# pressure_gage.net
KiCad netlist of a schematic drawn in Altium Designer
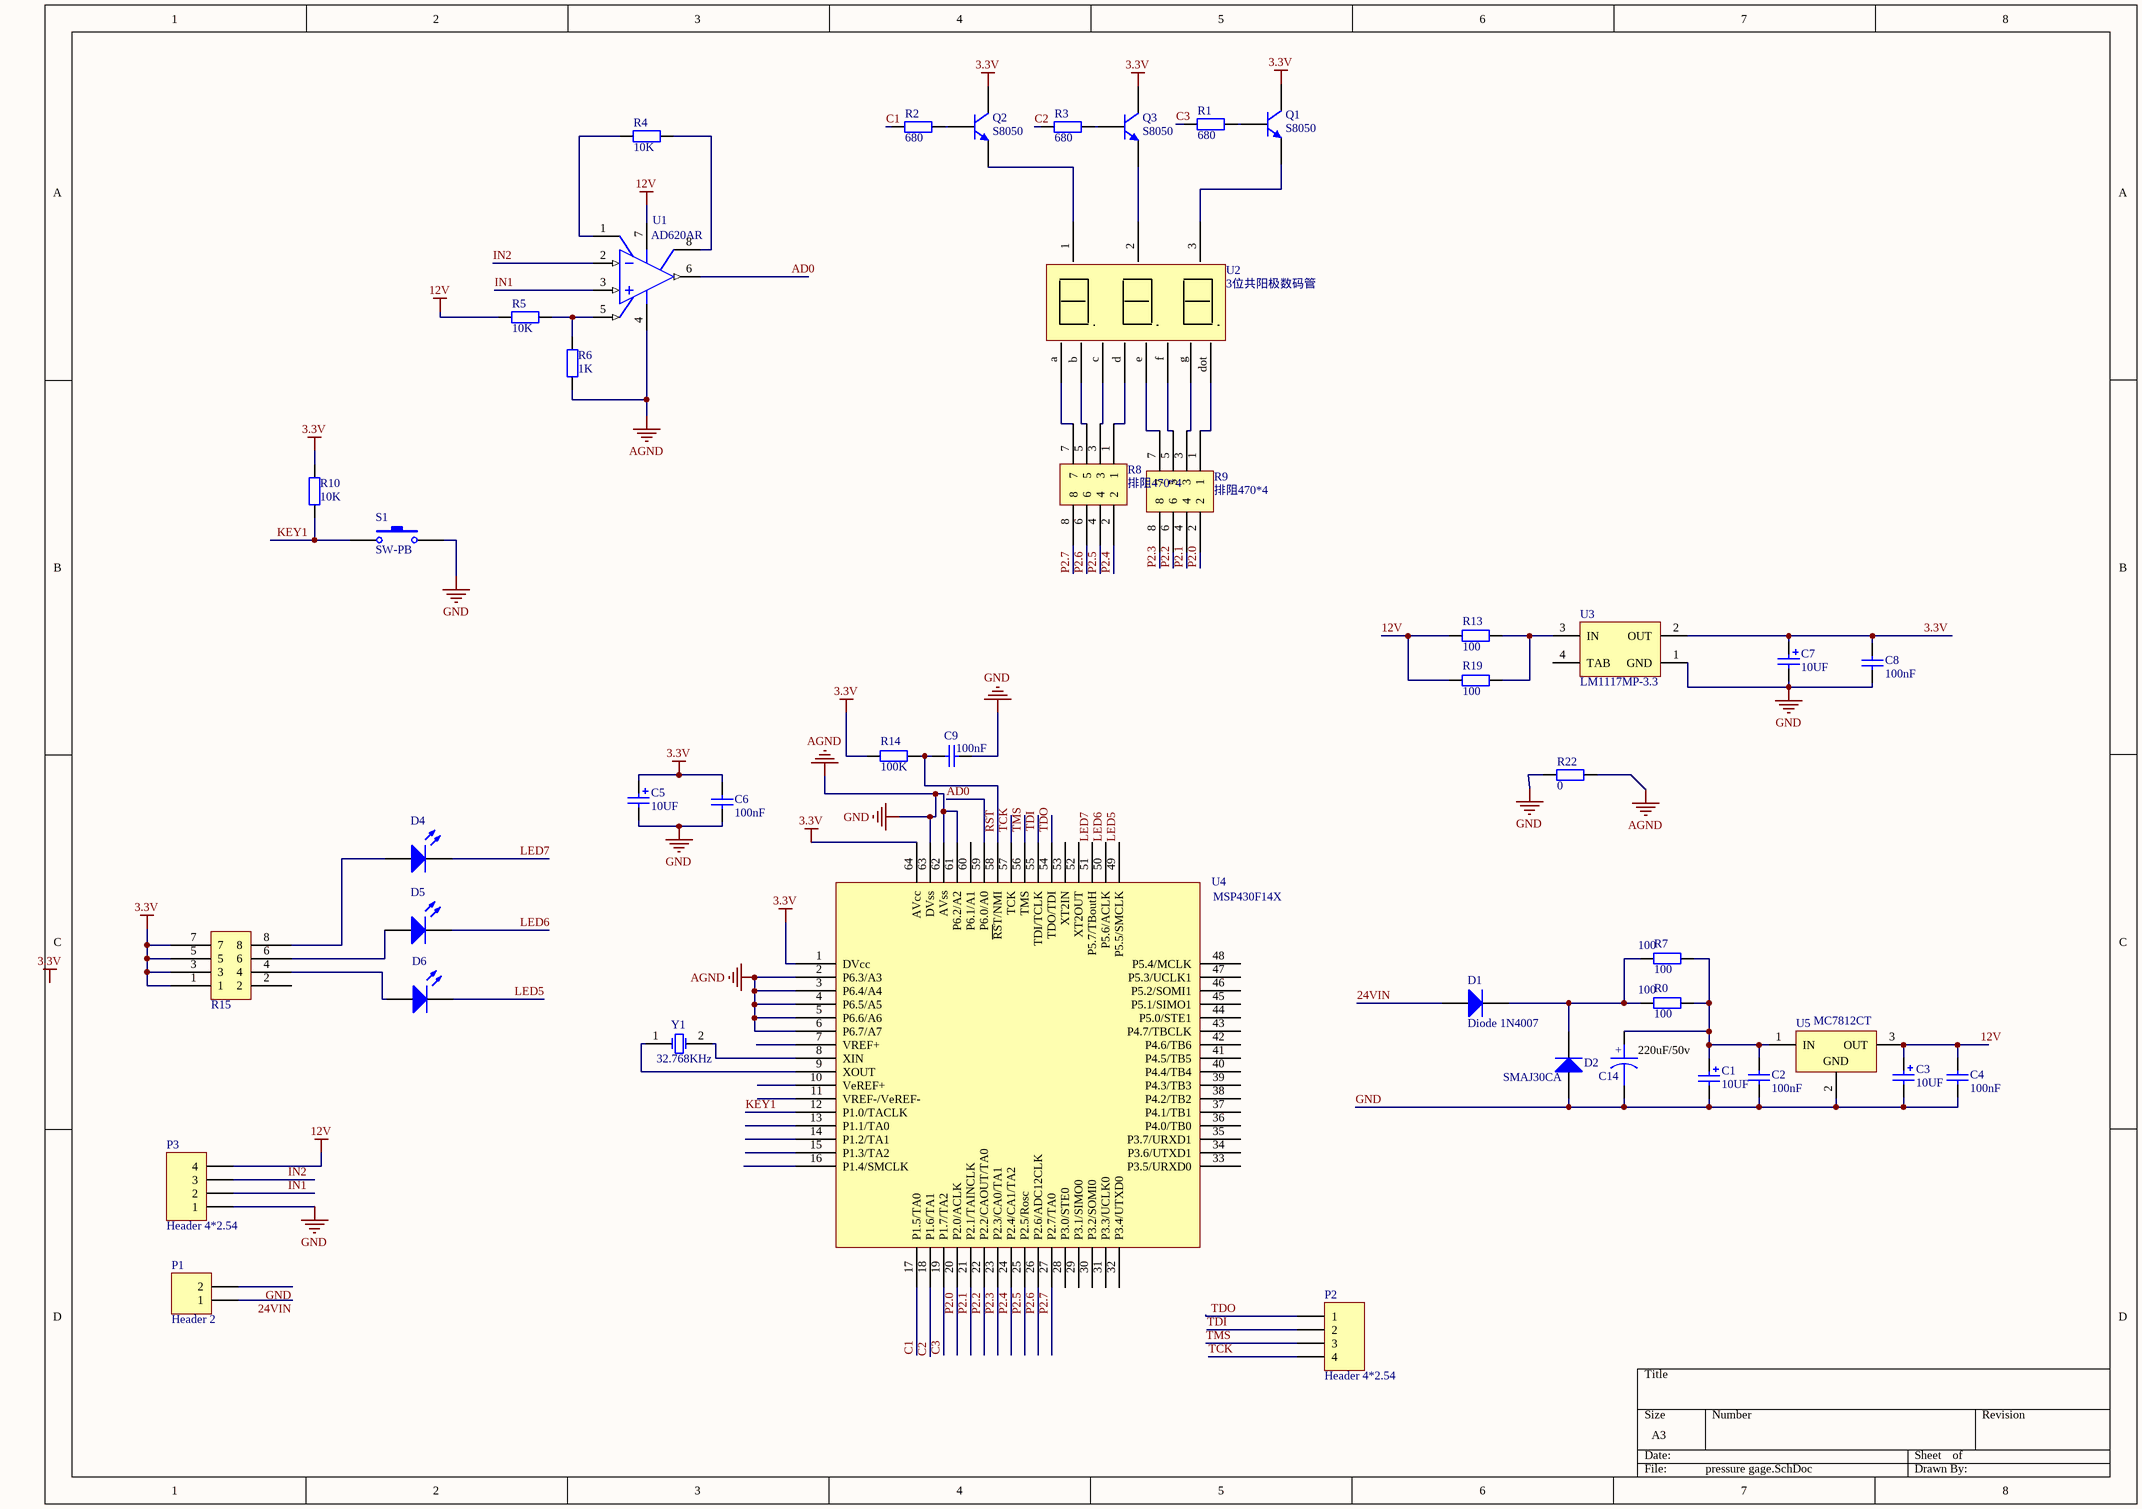
[diagram p0: pressure gage.SchDoc]

(export (version "E")
  (design (tool "Eeschema 10.0.6"))
  (components
    (comp (ref "C1")
      (value "10UF")
      (footprint "3216")
      (description "Polarized Capacitor (Axial)")
      (fields (field (name "Comment") "10uf") (field (name "PUBLISHER") "Altium Limited"))
      (libsource (lib "Miscellaneous Devices") (part "Cap Pol2"))
    )
    (comp (ref "C2")
      (value "100nF")
      (footprint "0805_C_Y")
      (description "Capacitor")
      (fields (field (name "Comment") "100nf") (field (name "PUBLISHER") "Altium Limited"))
      (libsource (lib "Miscellaneous Devices") (part "Cap"))
    )
    (comp (ref "C3")
      (value "10UF")
      (footprint "3216")
      (description "Polarized Capacitor (Axial)")
      (fields (field (name "Comment") "10uf") (field (name "PUBLISHER") "Altium Limited"))
      (libsource (lib "Miscellaneous Devices") (part "Cap Pol2"))
    )
    (comp (ref "C4")
      (value "100nF")
      (footprint "0805_C_Y")
      (description "Capacitor")
      (fields (field (name "Comment") "100nf") (field (name "PUBLISHER") "Altium Limited"))
      (libsource (lib "Miscellaneous Devices") (part "Cap"))
    )
    (comp (ref "C5")
      (value "10UF")
      (footprint "3216")
      (description "Polarized Capacitor (Axial)")
      (fields (field (name "Comment") "10uf") (field (name "PUBLISHER") "Altium Limited"))
      (libsource (lib "Miscellaneous Devices") (part "Cap Pol2"))
    )
    (comp (ref "C6")
      (value "100nF")
      (footprint "0603AC")
      (description "Capacitor")
      (fields (field (name "Comment") "100nf") (field (name "PUBLISHER") "Altium Limited"))
      (libsource (lib "Miscellaneous Devices") (part "Cap"))
    )
    (comp (ref "C7")
      (value "10UF")
      (footprint "3216")
      (description "Polarized Capacitor (Axial)")
      (fields (field (name "Comment") "10uf") (field (name "PUBLISHER") "Altium Limited"))
      (libsource (lib "Miscellaneous Devices") (part "Cap Pol2"))
    )
    (comp (ref "C8")
      (value "100nF")
      (footprint "0603AC")
      (description "Capacitor")
      (fields (field (name "Comment") "100nf") (field (name "PUBLISHER") "Altium Limited"))
      (libsource (lib "Miscellaneous Devices") (part "Cap"))
    )
    (comp (ref "C9")
      (value "100nF")
      (footprint "0603AC")
      (description "Capacitor")
      (fields (field (name "Comment") "100nf") (field (name "PUBLISHER") "Altium Limited"))
      (libsource (lib "Miscellaneous Devices") (part "Cap"))
    )
    (comp (ref "C14")
      (value "220uF/50v")
      (footprint "D50")
      (description "Capacitor")
      (libsource (lib "*") (part "CAPACITOR POL"))
    )
    (comp (ref "D1")
      (value "Diode 1N4007")
      (footprint "DO-214")
      (description "1 Amp General Purpose Rectifier")
      (fields (field (name "PUBLISHER") "Altium Limited"))
      (libsource (lib "Miscellaneous Devices") (part "Diode 1N4007"))
    )
    (comp (ref "D2")
      (value "SMAJ30CA")
      (footprint "1812")
      (description "3 Amp General Purpose Rectifier")
      (fields (field (name "PUBLISHER") "Altium Limited"))
      (libsource (lib "Miscellaneous Devices") (part "Diode 1N5402"))
    )
    (comp (ref "D4")
      (value "LED")
      (footprint "LED")
      (description "Typical INFRARED GaAs LED")
      (fields (field (name "PUBLISHER") "Altium Limited"))
      (libsource (lib "Miscellaneous Devices") (part "LED0"))
    )
    (comp (ref "D5")
      (value "LED")
      (footprint "LED")
      (description "Typical INFRARED GaAs LED")
      (fields (field (name "PUBLISHER") "Altium Limited"))
      (libsource (lib "Miscellaneous Devices") (part "LED0"))
    )
    (comp (ref "D6")
      (value "LED")
      (footprint "LED")
      (description "Typical INFRARED GaAs LED")
      (fields (field (name "PUBLISHER") "Altium Limited"))
      (libsource (lib "Miscellaneous Devices") (part "LED0"))
    )
    (comp (ref "P1")
      (value "Header 2")
      (footprint "HDR1X2")
      (description "Header, 2-Pin")
      (fields (field (name "PUBLISHER") "Altium Limited"))
      (libsource (lib "Miscellaneous Connectors") (part "Header 2"))
    )
    (comp (ref "P2")
      (value "Header 4*2.54")
      (footprint "HDR1X4")
      (description "Header, 4-Pin")
      (fields (field (name "PUBLISHER") "Altium Limited"))
      (libsource (lib "") (part "Header 4_1"))
    )
    (comp (ref "P3")
      (value "Header 4*2.54")
      (footprint "HDR1X4")
      (description "Header, 4-Pin")
      (fields (field (name "PUBLISHER") "Altium Limited"))
      (libsource (lib "Miscellaneous Connectors") (part "Header 4"))
    )
    (comp (ref "Q1")
      (value "S8050")
      (footprint "SOT-23_Y")
      (description "NPN General Purpose Amplifier")
      (fields (field (name "PUBLISHER") "Altium Limited"))
      (libsource (lib "Miscellaneous Devices") (part "2N3904"))
    )
    (comp (ref "Q2")
      (value "S8050")
      (footprint "SOT-23_Y")
      (description "NPN General Purpose Amplifier")
      (fields (field (name "PUBLISHER") "Altium Limited"))
      (libsource (lib "Miscellaneous Devices") (part "2N3904"))
    )
    (comp (ref "Q3")
      (value "S8050")
      (footprint "SOT-23_Y")
      (description "NPN General Purpose Amplifier")
      (fields (field (name "PUBLISHER") "Altium Limited"))
      (libsource (lib "Miscellaneous Devices") (part "2N3904"))
    )
    (comp (ref "R0")
      (value "100")
      (footprint "1206")
      (description "Resistor")
      (fields (field (name "ALTIUM_VALUE") "100") (field (name "PUBLISHER") "Altium Limited"))
      (libsource (lib "") (part "Res2_1"))
    )
    (comp (ref "R1")
      (value "680")
      (footprint "0603AR")
      (description "Resistor")
      (fields (field (name "Comment") "330") (field (name "PUBLISHER") "Altium Limited"))
      (libsource (lib "Miscellaneous Devices") (part "Res2"))
    )
    (comp (ref "R2")
      (value "680")
      (footprint "0603AR")
      (description "Resistor")
      (fields (field (name "Comment") "330") (field (name "PUBLISHER") "Altium Limited"))
      (libsource (lib "Miscellaneous Devices") (part "Res2"))
    )
    (comp (ref "R3")
      (value "680")
      (footprint "0603AR")
      (description "Resistor")
      (fields (field (name "Comment") "330") (field (name "PUBLISHER") "Altium Limited"))
      (libsource (lib "Miscellaneous Devices") (part "Res2"))
    )
    (comp (ref "R4")
      (value "10K")
      (footprint "0603AR")
      (description "Resistor")
      (fields (field (name "Comment") "10k") (field (name "PUBLISHER") "Altium Limited"))
      (libsource (lib "") (part "Res2_1"))
    )
    (comp (ref "R5")
      (value "10K")
      (footprint "0603AR")
      (description "Resistor")
      (fields (field (name "Comment") "10k") (field (name "PUBLISHER") "Altium Limited"))
      (libsource (lib "Miscellaneous Devices") (part "Res2"))
    )
    (comp (ref "R6")
      (value "1K")
      (footprint "0603AR")
      (description "Resistor")
      (fields (field (name "Comment") "1k") (field (name "PUBLISHER") "Altium Limited"))
      (libsource (lib "") (part "Res2_2"))
    )
    (comp (ref "R7")
      (value "100")
      (footprint "1206")
      (description "Resistor")
      (fields (field (name "ALTIUM_VALUE") "100") (field (name "PUBLISHER") "Altium Limited"))
      (libsource (lib "") (part "Res2_1"))
    )
    (comp (ref "R8") (value "排阻470*4") (footprint "8P4R_0603") (libsource (lib "xianshi") (part "排阻 8P4R")))
    (comp (ref "R9") (value "排阻470*4") (footprint "8P4R_0603") (libsource (lib "xianshi") (part "排阻 8P4R")))
    (comp (ref "R10")
      (value "10K")
      (footprint "0603")
      (description "Resistor")
      (fields (field (name "Comment") "1k") (field (name "PUBLISHER") "Altium Limited"))
      (libsource (lib "") (part "Res2_2"))
    )
    (comp (ref "R13")
      (value "100")
      (footprint "1206")
      (description "Resistor")
      (fields (field (name "PUBLISHER") "Altium Limited"))
      (libsource (lib "") (part "Res2_1"))
    )
    (comp (ref "R14")
      (value "100K")
      (footprint "0603AR")
      (description "Resistor")
      (fields (field (name "Comment") "100k") (field (name "PUBLISHER") "Altium Limited"))
      (libsource (lib "") (part "Res2_1"))
    )
    (comp (ref "R15") (value "排阻470*4") (footprint "8P4R_0603") (libsource (lib "biao2") (part "排阻 8P4R")))
    (comp (ref "R19")
      (value "100")
      (footprint "1206")
      (description "Resistor")
      (fields (field (name "PUBLISHER") "Altium Limited"))
      (libsource (lib "") (part "Res2_1"))
    )
    (comp (ref "R22")
      (value "0")
      (footprint "0603AR")
      (description "Resistor")
      (fields (field (name "PUBLISHER") "Altium Limited"))
      (libsource (lib "Miscellaneous Devices") (part "Res2"))
    )
    (comp (ref "S1")
      (value "SW-PB")
      (footprint "SW-SMD1")
      (description "Switch")
      (fields (field (name "PUBLISHER") "Altium Limited"))
      (libsource (lib "Miscellaneous Devices") (part "SW-PB"))
    )
    (comp (ref "U1")
      (value "AD620AR")
      (footprint "SO-8_Y")
      (description "Low-Cost, Low-Power Instrumentation Amplifier")
      (fields (field (name "PUBLISHER") "Altium Limited"))
      (libsource (lib "AD Instrumentation Amplifier") (part "AD620AR"))
    )
    (comp (ref "U2") (value "3位共阳极数码管") (footprint "3位数码管0.56") (libsource (lib "kelei") (part "3位共阳极数码管")))
    (comp (ref "U3")
      (value "LM1117MP-3.3")
      (footprint "SOT89M")
      (description "800mA Low-Dropout Linear Regulator")
      (fields
        (field (name "MANUFACTURER") "National Semiconductor")
        (field (name "DIGIKEYPARTNUMBER") "LM1117MP-3.3CT-ND")
        (field (name "PUBLISHER") "Altium Limited")
      )
      (libsource (lib "NSC LDO") (part "LM1117MP-3.3"))
    )
    (comp (ref "U4")
      (value "MSP430F14X")
      (footprint "S-PQFP-G64_Y")
      (libsource (lib "MSP430原理图") (part "MSP430F14X"))
    )
    (comp (ref "U5")
      (value "MC7812CT")
      (footprint "SOT89M")
      (description "Three-Terminal Positive Voltage Regulator")
      (fields (field (name "PUBLISHER") "Altium Limited"))
      (libsource (lib "ON Semi Power Mgt Voltage Regulator") (part "MC7812CT"))
    )
    (comp (ref "Y1")
      (value "32.768KHz")
      (footprint "Crastal_32.768_Y")
      (description "Crystal Oscillator")
      (fields (field (name "Comment") "晶振32.768k") (field (name "PUBLISHER") "Altium Limited"))
      (libsource (lib "Miscellaneous Devices") (part "XTAL"))
    )
  )
  (nets
    (net (code "1") (name "/24VIN") (class "Default")
      (node (ref "D1") (pin "1") (pinfunction "A_1") (pintype "passive"))
      (node (ref "P1") (pin "1") (pinfunction "1_1") (pintype "passive"))
    )
    (net (code "2") (name "/AD0") (class "Default")
      (node (ref "U1") (pin "6") (pinfunction "OUT_6") (pintype "output"))
      (node (ref "U4") (pin "59") (pinfunction "P6.0/A0_59") (pintype "power_in"))
    )
    (net (code "3") (name "/C1") (class "Default")
      (node (ref "R2") (pin "2") (pinfunction "2_2") (pintype "passive"))
      (node (ref "U4") (pin "17") (pinfunction "P1.5/TA0_17") (pintype "power_in"))
    )
    (net (code "4") (name "/C2") (class "Default")
      (node (ref "R3") (pin "2") (pinfunction "2_2") (pintype "passive"))
      (node (ref "U4") (pin "18") (pinfunction "P1.6/TA1_18") (pintype "power_in"))
    )
    (net (code "5") (name "/C3") (class "Default")
      (node (ref "R1") (pin "2") (pinfunction "2_2") (pintype "passive"))
      (node (ref "U4") (pin "19") (pinfunction "P1.7/TA2_19") (pintype "power_in"))
    )
    (net (code "6") (name "/IN1") (class "Default")
      (node (ref "P3") (pin "2") (pinfunction "2_2") (pintype "passive"))
      (node (ref "U1") (pin "3") (pinfunction "+IN_3") (pintype "input"))
    )
    (net (code "7") (name "/IN2") (class "Default")
      (node (ref "P3") (pin "3") (pinfunction "3_3") (pintype "passive"))
      (node (ref "U1") (pin "2") (pinfunction "-IN_2") (pintype "input"))
    )
    (net (code "8") (name "/KEY1") (class "Default")
      (node (ref "R10") (pin "1") (pinfunction "1_1") (pintype "passive"))
      (node (ref "S1") (pin "1") (pinfunction "1_1") (pintype "passive"))
      (node (ref "U4") (pin "12") (pinfunction "P1.0/TACLK_12") (pintype "power_in"))
    )
    (net (code "9") (name "/LED5") (class "Default")
      (node (ref "D6") (pin "2") (pinfunction "K_2") (pintype "passive"))
      (node (ref "U4") (pin "49") (pinfunction "P5.5/SMCLK_49") (pintype "power_in"))
    )
    (net (code "10") (name "/LED6") (class "Default")
      (node (ref "D5") (pin "2") (pinfunction "K_2") (pintype "passive"))
      (node (ref "U4") (pin "50") (pinfunction "P5.6/ACLK_50") (pintype "power_in"))
    )
    (net (code "11") (name "/LED7") (class "Default")
      (node (ref "D4") (pin "2") (pinfunction "K_2") (pintype "passive"))
      (node (ref "U4") (pin "51") (pinfunction "P5.7/TBoutH_51") (pintype "power_in"))
    )
    (net (code "12") (name "/P2.0") (class "Default")
      (node (ref "R9") (pin "2") (pinfunction "2_2") (pintype "passive"))
      (node (ref "U4") (pin "20") (pinfunction "P2.0/ACLK_20") (pintype "power_in"))
    )
    (net (code "13") (name "/P2.1") (class "Default")
      (node (ref "R9") (pin "4") (pinfunction "4_4") (pintype "passive"))
      (node (ref "U4") (pin "21") (pinfunction "P2.1/TAINCLK_21") (pintype "power_in"))
    )
    (net (code "14") (name "/P2.2") (class "Default")
      (node (ref "R9") (pin "6") (pinfunction "6_6") (pintype "passive"))
      (node (ref "U4") (pin "22") (pinfunction "P2.2/CAOUT/TA0_22") (pintype "power_in"))
    )
    (net (code "15") (name "/P2.3") (class "Default")
      (node (ref "R9") (pin "8") (pinfunction "8_8") (pintype "passive"))
      (node (ref "U4") (pin "23") (pinfunction "P2.3/CA0/TA1_23") (pintype "power_in"))
    )
    (net (code "16") (name "/P2.4") (class "Default")
      (node (ref "R8") (pin "2") (pinfunction "2_2") (pintype "passive"))
      (node (ref "U4") (pin "24") (pinfunction "P2.4/CA1/TA2_24") (pintype "power_in"))
    )
    (net (code "17") (name "/P2.5") (class "Default")
      (node (ref "R8") (pin "4") (pinfunction "4_4") (pintype "passive"))
      (node (ref "U4") (pin "25") (pinfunction "P2.5/Rosc_25") (pintype "power_in"))
    )
    (net (code "18") (name "/P2.6") (class "Default")
      (node (ref "R8") (pin "6") (pinfunction "6_6") (pintype "passive"))
      (node (ref "U4") (pin "26") (pinfunction "P2.6/ADC12CLK_26") (pintype "power_in"))
    )
    (net (code "19") (name "/P2.7") (class "Default")
      (node (ref "R8") (pin "8") (pinfunction "8_8") (pintype "passive"))
      (node (ref "U4") (pin "27") (pinfunction "P2.7/TA0_27") (pintype "power_in"))
    )
    (net (code "20") (name "/RST") (class "Default")
      (node (ref "C9") (pin "2") (pinfunction "2_2") (pintype "passive"))
      (node (ref "R14") (pin "2") (pinfunction "2_2") (pintype "passive"))
      (node (ref "U4") (pin "58") (pinfunction "~{RS}T/NMI_58") (pintype "power_in"))
    )
    (net (code "21") (name "/TCK") (class "Default")
      (node (ref "P2") (pin "4") (pinfunction "4_4") (pintype "passive"))
      (node (ref "U4") (pin "57") (pinfunction "TCK_57") (pintype "power_in"))
    )
    (net (code "22") (name "/TDI") (class "Default")
      (node (ref "P2") (pin "2") (pinfunction "2_2") (pintype "passive"))
      (node (ref "U4") (pin "55") (pinfunction "TDI/TCLK_55") (pintype "power_in"))
    )
    (net (code "23") (name "/TDO") (class "Default")
      (node (ref "P2") (pin "1") (pinfunction "1_1") (pintype "passive"))
      (node (ref "U4") (pin "54") (pinfunction "TDO/TDI_54") (pintype "power_in"))
    )
    (net (code "24") (name "/TMS") (class "Default")
      (node (ref "P2") (pin "3") (pinfunction "3_3") (pintype "passive"))
      (node (ref "U4") (pin "56") (pinfunction "TMS_56") (pintype "power_in"))
    )
    (net (code "25") (name "3.3V") (class "Default")
      (node (ref "C5") (pin "1") (pinfunction "1_1") (pintype "passive"))
      (node (ref "C6") (pin "1") (pinfunction "1_1") (pintype "passive"))
      (node (ref "C7") (pin "1") (pinfunction "1_1") (pintype "passive"))
      (node (ref "C8") (pin "1") (pinfunction "1_1") (pintype "passive"))
      (node (ref "Q1") (pin "3") (pinfunction "C_3") (pintype "passive"))
      (node (ref "Q2") (pin "3") (pinfunction "C_3") (pintype "passive"))
      (node (ref "Q3") (pin "3") (pinfunction "C_3") (pintype "passive"))
      (node (ref "R10") (pin "2") (pinfunction "2_2") (pintype "passive"))
      (node (ref "R14") (pin "1") (pinfunction "1_1") (pintype "passive"))
      (node (ref "R15") (pin "1") (pinfunction "1_1") (pintype "passive"))
      (node (ref "R15") (pin "3") (pinfunction "3_3") (pintype "passive"))
      (node (ref "R15") (pin "5") (pinfunction "5_5") (pintype "passive"))
      (node (ref "R15") (pin "7") (pinfunction "7_7") (pintype "passive"))
      (node (ref "U3") (pin "2") (pinfunction "OUT_2") (pintype "power_in"))
      (node (ref "U4") (pin "1") (pinfunction "DVcc_1") (pintype "power_in"))
      (node (ref "U4") (pin "64") (pinfunction "AVcc_64") (pintype "power_in"))
    )
    (net (code "26") (name "12V") (class "Default")
      (node (ref "C3") (pin "1") (pinfunction "1_1") (pintype "passive"))
      (node (ref "C4") (pin "1") (pinfunction "1_1") (pintype "passive"))
      (node (ref "P3") (pin "4") (pinfunction "4_4") (pintype "passive"))
      (node (ref "R13") (pin "1") (pinfunction "1_1") (pintype "passive"))
      (node (ref "R19") (pin "1") (pinfunction "1_1") (pintype "passive"))
      (node (ref "R5") (pin "2") (pinfunction "2_2") (pintype "passive"))
      (node (ref "U1") (pin "7") (pinfunction "V+_7") (pintype "power_in"))
      (node (ref "U5") (pin "3") (pinfunction "OUT_3") (pintype "power_in"))
    )
    (net (code "27") (name "AGND") (class "Default")
      (node (ref "C1") (pin "2") (pinfunction "2_2") (pintype "passive"))
      (node (ref "C14") (pin "2") (pinfunction "2_2") (pintype "passive"))
      (node (ref "C2") (pin "2") (pinfunction "2_2") (pintype "passive"))
      (node (ref "C3") (pin "2") (pinfunction "2_2") (pintype "passive"))
      (node (ref "C4") (pin "2") (pinfunction "2_2") (pintype "passive"))
      (node (ref "C5") (pin "2") (pinfunction "2_2") (pintype "passive"))
      (node (ref "C6") (pin "2") (pinfunction "2_2") (pintype "passive"))
      (node (ref "C7") (pin "2") (pinfunction "2_2") (pintype "passive"))
      (node (ref "C8") (pin "2") (pinfunction "2_2") (pintype "passive"))
      (node (ref "C9") (pin "1") (pinfunction "1_1") (pintype "passive"))
      (node (ref "D2") (pin "1") (pinfunction "A_1") (pintype "passive"))
      (node (ref "P1") (pin "2") (pinfunction "2_2") (pintype "passive"))
      (node (ref "P3") (pin "1") (pinfunction "1_1") (pintype "passive"))
      (node (ref "R22") (pin "1") (pinfunction "1_1") (pintype "passive"))
      (node (ref "R22") (pin "2") (pinfunction "2_2") (pintype "passive"))
      (node (ref "R6") (pin "1") (pinfunction "1_1") (pintype "passive"))
      (node (ref "S1") (pin "2") (pinfunction "2_2") (pintype "passive"))
      (node (ref "U1") (pin "4") (pinfunction "V-_4") (pintype "power_in"))
      (node (ref "U3") (pin "1") (pinfunction "GND_1") (pintype "power_in"))
      (node (ref "U4") (pin "2") (pinfunction "P6.3/A3_2") (pintype "power_in"))
      (node (ref "U4") (pin "3") (pinfunction "P6.4/A4_3") (pintype "power_in"))
      (node (ref "U4") (pin "4") (pinfunction "P6.5/A5_4") (pintype "power_in"))
      (node (ref "U4") (pin "5") (pinfunction "P6.6/A6_5") (pintype "power_in"))
      (node (ref "U4") (pin "6") (pinfunction "P6.7/A7_6") (pintype "power_in"))
      (node (ref "U4") (pin "61") (pinfunction "P6.2/A2_61") (pintype "power_in"))
      (node (ref "U4") (pin "62") (pinfunction "AVss_62") (pintype "power_in"))
      (node (ref "U4") (pin "63") (pinfunction "DVss_63") (pintype "power_in"))
      (node (ref "U5") (pin "2") (pinfunction "GND_2") (pintype "power_in"))
    )
    (net (code "28") (name "Net-(D1-K)") (class "Default")
      (node (ref "D1") (pin "2") (pinfunction "K_2") (pintype "passive"))
      (node (ref "D2") (pin "2") (pinfunction "K_2") (pintype "passive"))
      (node (ref "R0") (pin "1") (pinfunction "1_1") (pintype "passive"))
      (node (ref "R7") (pin "1") (pinfunction "1_1") (pintype "passive"))
    )
    (net (code "29") (name "Net-(D4-A)") (class "Default")
      (node (ref "D4") (pin "1") (pinfunction "A_1") (pintype "passive"))
      (node (ref "R15") (pin "8") (pinfunction "8_8") (pintype "passive"))
    )
    (net (code "30") (name "Net-(D5-A)") (class "Default")
      (node (ref "D5") (pin "1") (pinfunction "A_1") (pintype "passive"))
      (node (ref "R15") (pin "6") (pinfunction "6_6") (pintype "passive"))
    )
    (net (code "31") (name "Net-(D6-A)") (class "Default")
      (node (ref "D6") (pin "1") (pinfunction "A_1") (pintype "passive"))
      (node (ref "R15") (pin "4") (pinfunction "4_4") (pintype "passive"))
    )
    (net (code "32") (name "Net-(Q1-B)") (class "Default")
      (node (ref "Q1") (pin "1") (pinfunction "B_1") (pintype "passive"))
      (node (ref "R1") (pin "1") (pinfunction "1_1") (pintype "passive"))
    )
    (net (code "33") (name "Net-(Q1-E)") (class "Default")
      (node (ref "Q1") (pin "2") (pinfunction "E_2") (pintype "passive"))
      (node (ref "U2") (pin "3") (pinfunction "3_3") (pintype "passive"))
    )
    (net (code "34") (name "Net-(Q2-B)") (class "Default")
      (node (ref "Q2") (pin "1") (pinfunction "B_1") (pintype "passive"))
      (node (ref "R2") (pin "1") (pinfunction "1_1") (pintype "passive"))
    )
    (net (code "35") (name "Net-(Q2-E)") (class "Default")
      (node (ref "Q2") (pin "2") (pinfunction "E_2") (pintype "passive"))
      (node (ref "U2") (pin "1") (pinfunction "1_1") (pintype "passive"))
    )
    (net (code "36") (name "Net-(Q3-B)") (class "Default")
      (node (ref "Q3") (pin "1") (pinfunction "B_1") (pintype "passive"))
      (node (ref "R3") (pin "1") (pinfunction "1_1") (pintype "passive"))
    )
    (net (code "37") (name "Net-(Q3-E)") (class "Default")
      (node (ref "Q3") (pin "2") (pinfunction "E_2") (pintype "passive"))
      (node (ref "U2") (pin "2") (pinfunction "2_2") (pintype "passive"))
    )
    (net (code "38") (name "Net-(R4-Pad1)") (class "Default")
      (node (ref "R4") (pin "1") (pinfunction "1_1") (pintype "passive"))
      (node (ref "U1") (pin "1") (pinfunction "RG_1") (pintype "passive"))
    )
    (net (code "39") (name "Net-(R4-Pad2)") (class "Default")
      (node (ref "R4") (pin "2") (pinfunction "2_2") (pintype "passive"))
      (node (ref "U1") (pin "8") (pinfunction "RG_8") (pintype "passive"))
    )
    (net (code "40") (name "Net-(R8-Pad1)") (class "Default")
      (node (ref "R8") (pin "1") (pinfunction "1_1") (pintype "passive"))
      (node (ref "U2") (pin "d") (pinfunction "d_d") (pintype "passive"))
    )
    (net (code "41") (name "Net-(R8-Pad3)") (class "Default")
      (node (ref "R8") (pin "3") (pinfunction "3_3") (pintype "passive"))
      (node (ref "U2") (pin "c") (pinfunction "c_c") (pintype "passive"))
    )
    (net (code "42") (name "Net-(R8-Pad5)") (class "Default")
      (node (ref "R8") (pin "5") (pinfunction "5_5") (pintype "passive"))
      (node (ref "U2") (pin "b") (pinfunction "b_b") (pintype "passive"))
    )
    (net (code "43") (name "Net-(R8-Pad7)") (class "Default")
      (node (ref "R8") (pin "7") (pinfunction "7_7") (pintype "passive"))
      (node (ref "U2") (pin "a") (pinfunction "a_a") (pintype "passive"))
    )
    (net (code "44") (name "Net-(R9-Pad1)") (class "Default")
      (node (ref "R9") (pin "1") (pinfunction "1_1") (pintype "passive"))
      (node (ref "U2") (pin "dot") (pinfunction "dot_dot") (pintype "passive"))
    )
    (net (code "45") (name "Net-(R9-Pad3)") (class "Default")
      (node (ref "R9") (pin "3") (pinfunction "3_3") (pintype "passive"))
      (node (ref "U2") (pin "g") (pinfunction "g_g") (pintype "passive"))
    )
    (net (code "46") (name "Net-(R9-Pad5)") (class "Default")
      (node (ref "R9") (pin "5") (pinfunction "5_5") (pintype "passive"))
      (node (ref "U2") (pin "f") (pinfunction "f_f") (pintype "passive"))
    )
    (net (code "47") (name "Net-(R9-Pad7)") (class "Default")
      (node (ref "R9") (pin "7") (pinfunction "7_7") (pintype "passive"))
      (node (ref "U2") (pin "e") (pinfunction "e_e") (pintype "passive"))
    )
    (net (code "48") (name "Net-(U1-REF)") (class "Default")
      (node (ref "R5") (pin "1") (pinfunction "1_1") (pintype "passive"))
      (node (ref "R6") (pin "2") (pinfunction "2_2") (pintype "passive"))
      (node (ref "U1") (pin "5") (pinfunction "REF_5") (pintype "input"))
    )
    (net (code "49") (name "Net-(U3-IN)") (class "Default")
      (node (ref "R13") (pin "2") (pinfunction "2_2") (pintype "passive"))
      (node (ref "R19") (pin "2") (pinfunction "2_2") (pintype "passive"))
      (node (ref "U3") (pin "3") (pinfunction "IN_3") (pintype "power_in"))
    )
    (net (code "50") (name "Net-(U4-XIN)") (class "Default")
      (node (ref "U4") (pin "8") (pinfunction "XIN_8") (pintype "power_in"))
      (node (ref "Y1") (pin "2") (pinfunction "OSC2_2") (pintype "passive"))
    )
    (net (code "51") (name "Net-(U4-XOUT)") (class "Default")
      (node (ref "U4") (pin "9") (pinfunction "XOUT_9") (pintype "power_in"))
      (node (ref "Y1") (pin "1") (pinfunction "OSC1_1") (pintype "passive"))
    )
    (net (code "52") (name "Net-(U5-IN)") (class "Default")
      (node (ref "C1") (pin "1") (pinfunction "1_1") (pintype "passive"))
      (node (ref "C14") (pin "1") (pinfunction "1_1") (pintype "passive"))
      (node (ref "C2") (pin "1") (pinfunction "1_1") (pintype "passive"))
      (node (ref "R0") (pin "2") (pinfunction "2_2") (pintype "passive"))
      (node (ref "R7") (pin "2") (pinfunction "2_2") (pintype "passive"))
      (node (ref "U5") (pin "1") (pinfunction "IN_1") (pintype "power_in"))
    )
    (net (code "53") (name "unconnected-(R15-Pad2)") (class "Default")
      (node (ref "R15") (pin "2") (pinfunction "2_2") (pintype "passive"))
    )
    (net (code "54") (name "unconnected-(U3-TAB-Pad4)") (class "Default")
      (node (ref "U3") (pin "4") (pinfunction "TAB_4") (pintype "power_in"))
    )
    (net (code "55") (name "unconnected-(U4-P1.1{slash}TA0-Pad13)") (class "Default")
      (node (ref "U4") (pin "13") (pinfunction "P1.1/TA0_13") (pintype "power_in"))
    )
    (net (code "56") (name "unconnected-(U4-P1.2{slash}TA1-Pad14)") (class "Default")
      (node (ref "U4") (pin "14") (pinfunction "P1.2/TA1_14") (pintype "power_in"))
    )
    (net (code "57") (name "unconnected-(U4-P1.3{slash}TA2-Pad15)") (class "Default")
      (node (ref "U4") (pin "15") (pinfunction "P1.3/TA2_15") (pintype "power_in"))
    )
    (net (code "58") (name "unconnected-(U4-P1.4{slash}SMCLK-Pad16)") (class "Default")
      (node (ref "U4") (pin "16") (pinfunction "P1.4/SMCLK_16") (pintype "power_in"))
    )
    (net (code "59") (name "unconnected-(U4-P3.0{slash}STE0-Pad28)") (class "Default")
      (node (ref "U4") (pin "28") (pinfunction "P3.0/STE0_28") (pintype "power_in"))
    )
    (net (code "60") (name "unconnected-(U4-P3.1{slash}SIMO0-Pad29)") (class "Default")
      (node (ref "U4") (pin "29") (pinfunction "P3.1/SIMO0_29") (pintype "power_in"))
    )
    (net (code "61") (name "unconnected-(U4-P3.2{slash}SOMI0-Pad30)") (class "Default")
      (node (ref "U4") (pin "30") (pinfunction "P3.2/SOMI0_30") (pintype "power_in"))
    )
    (net (code "62") (name "unconnected-(U4-P3.3{slash}UCLK0-Pad31)") (class "Default")
      (node (ref "U4") (pin "31") (pinfunction "P3.3/UCLK0_31") (pintype "power_in"))
    )
    (net (code "63") (name "unconnected-(U4-P3.4{slash}UTXD0-Pad32)") (class "Default")
      (node (ref "U4") (pin "32") (pinfunction "P3.4/UTXD0_32") (pintype "power_in"))
    )
    (net (code "64") (name "unconnected-(U4-P3.5{slash}URXD0-Pad33)") (class "Default")
      (node (ref "U4") (pin "33") (pinfunction "P3.5/URXD0_33") (pintype "power_in"))
    )
    (net (code "65") (name "unconnected-(U4-P3.6{slash}UTXD1-Pad34)") (class "Default")
      (node (ref "U4") (pin "34") (pinfunction "P3.6/UTXD1_34") (pintype "power_in"))
    )
    (net (code "66") (name "unconnected-(U4-P3.7{slash}URXD1-Pad35)") (class "Default")
      (node (ref "U4") (pin "35") (pinfunction "P3.7/URXD1_35") (pintype "power_in"))
    )
    (net (code "67") (name "unconnected-(U4-P4.0{slash}TB0-Pad36)") (class "Default")
      (node (ref "U4") (pin "36") (pinfunction "P4.0/TB0_36") (pintype "power_in"))
    )
    (net (code "68") (name "unconnected-(U4-P4.1{slash}TB1-Pad37)") (class "Default")
      (node (ref "U4") (pin "37") (pinfunction "P4.1/TB1_37") (pintype "power_in"))
    )
    (net (code "69") (name "unconnected-(U4-P4.2{slash}TB2-Pad38)") (class "Default")
      (node (ref "U4") (pin "38") (pinfunction "P4.2/TB2_38") (pintype "power_in"))
    )
    (net (code "70") (name "unconnected-(U4-P4.3{slash}TB3-Pad39)") (class "Default")
      (node (ref "U4") (pin "39") (pinfunction "P4.3/TB3_39") (pintype "power_in"))
    )
    (net (code "71") (name "unconnected-(U4-P4.4{slash}TB4-Pad40)") (class "Default")
      (node (ref "U4") (pin "40") (pinfunction "P4.4/TB4_40") (pintype "power_in"))
    )
    (net (code "72") (name "unconnected-(U4-P4.5{slash}TB5-Pad41)") (class "Default")
      (node (ref "U4") (pin "41") (pinfunction "P4.5/TB5_41") (pintype "power_in"))
    )
    (net (code "73") (name "unconnected-(U4-P4.6{slash}TB6-Pad42)") (class "Default")
      (node (ref "U4") (pin "42") (pinfunction "P4.6/TB6_42") (pintype "power_in"))
    )
    (net (code "74") (name "unconnected-(U4-P4.7{slash}TBCLK-Pad43)") (class "Default")
      (node (ref "U4") (pin "43") (pinfunction "P4.7/TBCLK_43") (pintype "power_in"))
    )
    (net (code "75") (name "unconnected-(U4-P5.0{slash}STE1-Pad44)") (class "Default")
      (node (ref "U4") (pin "44") (pinfunction "P5.0/STE1_44") (pintype "power_in"))
    )
    (net (code "76") (name "unconnected-(U4-P5.1{slash}SIMO1-Pad45)") (class "Default")
      (node (ref "U4") (pin "45") (pinfunction "P5.1/SIMO1_45") (pintype "power_in"))
    )
    (net (code "77") (name "unconnected-(U4-P5.2{slash}SOMI1-Pad46)") (class "Default")
      (node (ref "U4") (pin "46") (pinfunction "P5.2/SOMI1_46") (pintype "power_in"))
    )
    (net (code "78") (name "unconnected-(U4-P5.3{slash}UCLK1-Pad47)") (class "Default")
      (node (ref "U4") (pin "47") (pinfunction "P5.3/UCLK1_47") (pintype "power_in"))
    )
    (net (code "79") (name "unconnected-(U4-P5.4{slash}MCLK-Pad48)") (class "Default")
      (node (ref "U4") (pin "48") (pinfunction "P5.4/MCLK_48") (pintype "power_in"))
    )
    (net (code "80") (name "unconnected-(U4-P6.1{slash}A1-Pad60)") (class "Default")
      (node (ref "U4") (pin "60") (pinfunction "P6.1/A1_60") (pintype "power_in"))
    )
    (net (code "81") (name "unconnected-(U4-VREF+-Pad7)") (class "Default")
      (node (ref "U4") (pin "7") (pinfunction "VREF+_7") (pintype "power_in"))
    )
    (net (code "82") (name "unconnected-(U4-VREF-{slash}VeREF--Pad11)") (class "Default")
      (node (ref "U4") (pin "11") (pinfunction "VREF-/VeREF-_11") (pintype "power_in"))
    )
    (net (code "83") (name "unconnected-(U4-VeREF+-Pad10)") (class "Default")
      (node (ref "U4") (pin "10") (pinfunction "VeREF+_10") (pintype "power_in"))
    )
    (net (code "84") (name "unconnected-(U4-XT2IN-Pad53)") (class "Default")
      (node (ref "U4") (pin "53") (pinfunction "XT2IN_53") (pintype "power_in"))
    )
    (net (code "85") (name "unconnected-(U4-XT2OUT-Pad52)") (class "Default")
      (node (ref "U4") (pin "52") (pinfunction "XT2OUT_52") (pintype "power_in"))
    )
  )
)
